# Proto-Shield_v10.net
KiCad netlist of a schematic drawn in EAGLE
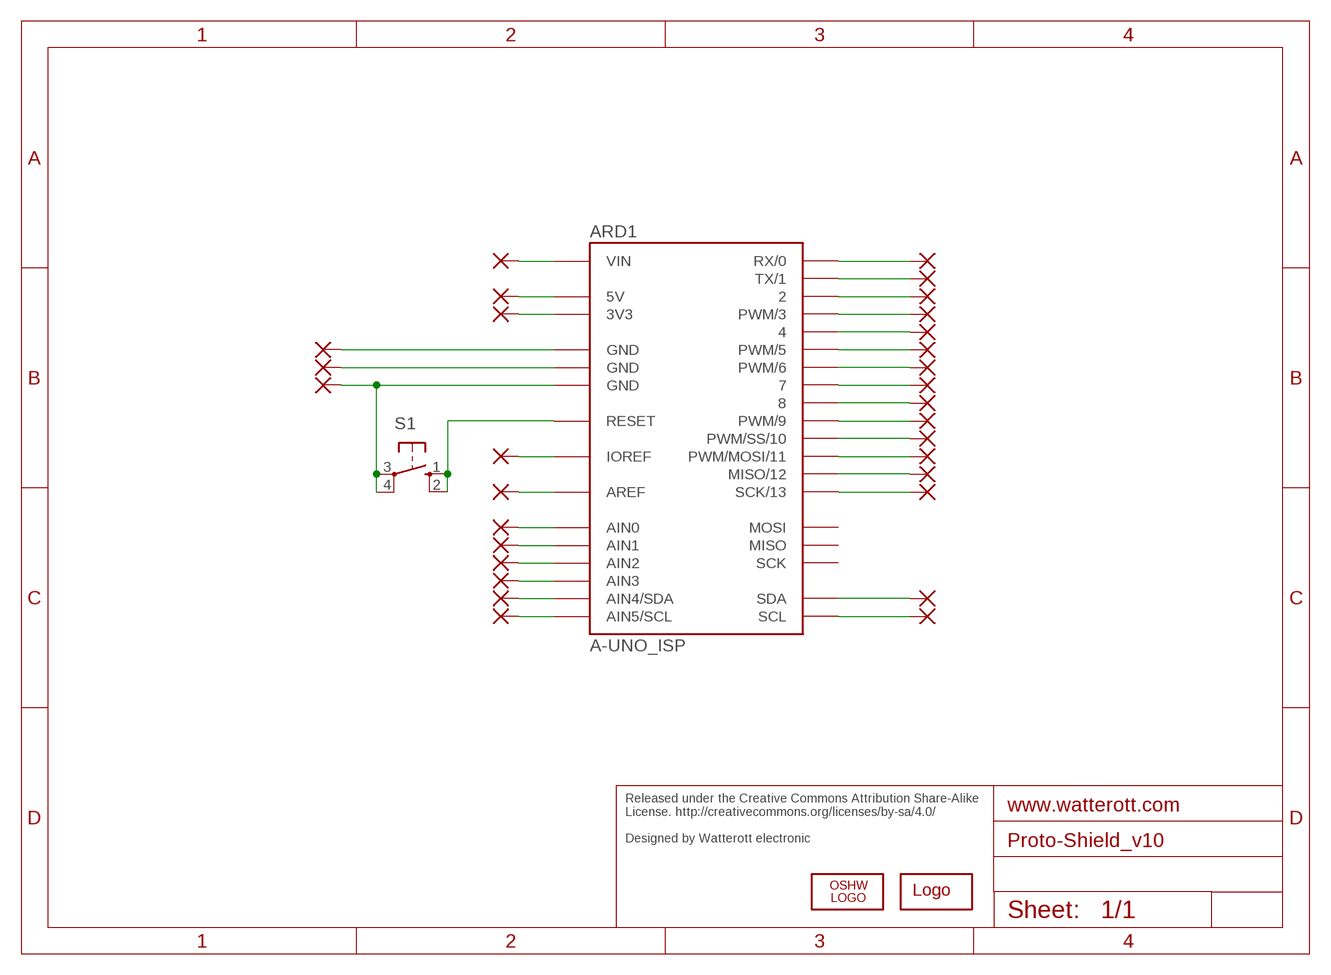
[diagram p0: schematic, sheet 1]

(export (version "E")
  (design (tool "Eeschema 10.0.6"))
  (components
    (comp (ref "ARD1")
      (value "A-UNO_ISP")
      (footprint "eagle-import:A-UNO-ISP")
      (libsource (lib "eagle-import") (part "A-UNO_ISP"))
    )
    (comp (ref "LOGO1")
      (value "OSHW_LOGOX0070")
      (footprint "eagle-import:OSHW_6X70")
      (libsource (lib "eagle-import") (part "OSHW_LOGOX0070"))
    )
    (comp (ref "LOGO2")
      (value "LOGO-S_PLACE_S")
      (footprint "eagle-import:SPARK_TPLACE_S")
      (libsource (lib "eagle-import") (part "LOGO-S_PLACE_S"))
    )
    (comp (ref "PAD1")
      (value "1,6/0,9")
      (footprint "eagle-import:1,6_0,9")
      (libsource (lib "eagle-import") (part "1,6/0,9"))
    )
    (comp (ref "PAD2")
      (value "1,6/0,9")
      (footprint "eagle-import:1,6_0,9")
      (libsource (lib "eagle-import") (part "1,6/0,9"))
    )
    (comp (ref "PAD3")
      (value "1,6/0,9")
      (footprint "eagle-import:1,6_0,9")
      (libsource (lib "eagle-import") (part "1,6/0,9"))
    )
    (comp (ref "PAD4")
      (value "1,6/0,9")
      (footprint "eagle-import:1,6_0,9")
      (libsource (lib "eagle-import") (part "1,6/0,9"))
    )
    (comp (ref "PAD5")
      (value "1,6/0,9")
      (footprint "eagle-import:1,6_0,9")
      (libsource (lib "eagle-import") (part "1,6/0,9"))
    )
    (comp (ref "PAD6")
      (value "1,6/0,9")
      (footprint "eagle-import:1,6_0,9")
      (libsource (lib "eagle-import") (part "1,6/0,9"))
    )
    (comp (ref "PAD7")
      (value "1,6/0,9")
      (footprint "eagle-import:1,6_0,9")
      (libsource (lib "eagle-import") (part "1,6/0,9"))
    )
    (comp (ref "PAD8")
      (value "1,6/0,9")
      (footprint "eagle-import:1,6_0,9")
      (libsource (lib "eagle-import") (part "1,6/0,9"))
    )
    (comp (ref "PAD9")
      (value "1,6/0,9")
      (footprint "eagle-import:1,6_0,9")
      (libsource (lib "eagle-import") (part "1,6/0,9"))
    )
    (comp (ref "PAD10")
      (value "1,6/0,9")
      (footprint "eagle-import:1,6_0,9")
      (libsource (lib "eagle-import") (part "1,6/0,9"))
    )
    (comp (ref "PAD11")
      (value "1,6/0,9")
      (footprint "eagle-import:1,6_0,9")
      (libsource (lib "eagle-import") (part "1,6/0,9"))
    )
    (comp (ref "PAD12")
      (value "1,6/0,9")
      (footprint "eagle-import:1,6_0,9")
      (libsource (lib "eagle-import") (part "1,6/0,9"))
    )
    (comp (ref "PAD13")
      (value "1,6/0,9")
      (footprint "eagle-import:1,6_0,9")
      (libsource (lib "eagle-import") (part "1,6/0,9"))
    )
    (comp (ref "PAD14")
      (value "1,6/0,9")
      (footprint "eagle-import:1,6_0,9")
      (libsource (lib "eagle-import") (part "1,6/0,9"))
    )
    (comp (ref "PAD15")
      (value "1,6/0,9")
      (footprint "eagle-import:1,6_0,9")
      (libsource (lib "eagle-import") (part "1,6/0,9"))
    )
    (comp (ref "PAD16")
      (value "1,6/0,9")
      (footprint "eagle-import:1,6_0,9")
      (libsource (lib "eagle-import") (part "1,6/0,9"))
    )
    (comp (ref "PAD17")
      (value "1,6/0,9")
      (footprint "eagle-import:1,6_0,9")
      (libsource (lib "eagle-import") (part "1,6/0,9"))
    )
    (comp (ref "PAD18")
      (value "1,6/0,9")
      (footprint "eagle-import:1,6_0,9")
      (libsource (lib "eagle-import") (part "1,6/0,9"))
    )
    (comp (ref "PAD19")
      (value "1,6/0,9")
      (footprint "eagle-import:1,6_0,9")
      (libsource (lib "eagle-import") (part "1,6/0,9"))
    )
    (comp (ref "PAD20")
      (value "1,6/0,9")
      (footprint "eagle-import:1,6_0,9")
      (libsource (lib "eagle-import") (part "1,6/0,9"))
    )
    (comp (ref "PAD21")
      (value "1,6/0,9")
      (footprint "eagle-import:1,6_0,9")
      (libsource (lib "eagle-import") (part "1,6/0,9"))
    )
    (comp (ref "PAD22")
      (value "1,6/0,9")
      (footprint "eagle-import:1,6_0,9")
      (libsource (lib "eagle-import") (part "1,6/0,9"))
    )
    (comp (ref "PAD23")
      (value "1,6/0,9")
      (footprint "eagle-import:1,6_0,9")
      (libsource (lib "eagle-import") (part "1,6/0,9"))
    )
    (comp (ref "PAD24")
      (value "1,6/0,9")
      (footprint "eagle-import:1,6_0,9")
      (libsource (lib "eagle-import") (part "1,6/0,9"))
    )
    (comp (ref "PAD25")
      (value "1,6/0,9")
      (footprint "eagle-import:1,6_0,9")
      (libsource (lib "eagle-import") (part "1,6/0,9"))
    )
    (comp (ref "PAD26")
      (value "1,6/0,9")
      (footprint "eagle-import:1,6_0,9")
      (libsource (lib "eagle-import") (part "1,6/0,9"))
    )
    (comp (ref "PAD27")
      (value "1,6/0,9")
      (footprint "eagle-import:1,6_0,9")
      (libsource (lib "eagle-import") (part "1,6/0,9"))
    )
    (comp (ref "PAD28")
      (value "1,6/0,9")
      (footprint "eagle-import:1,6_0,9")
      (libsource (lib "eagle-import") (part "1,6/0,9"))
    )
    (comp (ref "PAD29")
      (value "1,6/0,9")
      (footprint "eagle-import:1,6_0,9")
      (libsource (lib "eagle-import") (part "1,6/0,9"))
    )
    (comp (ref "PAD30")
      (value "1,6/0,9")
      (footprint "eagle-import:1,6_0,9")
      (libsource (lib "eagle-import") (part "1,6/0,9"))
    )
    (comp (ref "S1")
      (value "10-XX")
      (footprint "eagle-import:B3F-10XX")
      (fields (field (name "MPN") "B3F-1000"))
      (libsource (lib "eagle-import") (part "10-XX"))
    )
  )
  (nets
    (net (code "1") (name "Net-(ARD1-AIN0)") (class "Default")
      (node (ref "ARD1") (pin "A0") (pinfunction "AIN0_A0") (pintype "bidirectional"))
      (node (ref "PAD17") (pin "1") (pinfunction "P_1") (pintype "passive"))
    )
    (net (code "2") (name "Net-(ARD1-AIN1)") (class "Default")
      (node (ref "ARD1") (pin "A1") (pinfunction "AIN1_A1") (pintype "bidirectional"))
      (node (ref "PAD18") (pin "1") (pinfunction "P_1") (pintype "passive"))
    )
    (net (code "3") (name "Net-(ARD1-AIN2)") (class "Default")
      (node (ref "ARD1") (pin "A2") (pinfunction "AIN2_A2") (pintype "bidirectional"))
      (node (ref "PAD19") (pin "1") (pinfunction "P_1") (pintype "passive"))
    )
    (net (code "4") (name "Net-(ARD1-AIN3)") (class "Default")
      (node (ref "ARD1") (pin "A3") (pinfunction "AIN3_A3") (pintype "bidirectional"))
      (node (ref "PAD20") (pin "1") (pinfunction "P_1") (pintype "passive"))
    )
    (net (code "5") (name "Net-(ARD1-AIN4{slash}SDA)") (class "Default")
      (node (ref "ARD1") (pin "A4") (pinfunction "AIN4/SDA_A4") (pintype "bidirectional"))
      (node (ref "PAD21") (pin "1") (pinfunction "P_1") (pintype "passive"))
    )
    (net (code "6") (name "Net-(ARD1-AIN5{slash}SCL)") (class "Default")
      (node (ref "ARD1") (pin "A5") (pinfunction "AIN5/SCL_A5") (pintype "bidirectional"))
      (node (ref "PAD22") (pin "1") (pinfunction "P_1") (pintype "passive"))
    )
    (net (code "7") (name "Net-(ARD1-MISO{slash}12)") (class "Default")
      (node (ref "ARD1") (pin "12") (pinfunction "MISO/12_12") (pintype "bidirectional"))
      (node (ref "PAD13") (pin "1") (pinfunction "P_1") (pintype "passive"))
    )
    (net (code "8") (name "Net-(ARD1-PWM{slash}3)") (class "Default")
      (node (ref "ARD1") (pin "3") (pinfunction "PWM/3_3") (pintype "bidirectional"))
      (node (ref "PAD4") (pin "1") (pinfunction "P_1") (pintype "passive"))
    )
    (net (code "9") (name "Net-(ARD1-PWM{slash}5)") (class "Default")
      (node (ref "ARD1") (pin "5") (pinfunction "PWM/5_5") (pintype "bidirectional"))
      (node (ref "PAD6") (pin "1") (pinfunction "P_1") (pintype "passive"))
    )
    (net (code "10") (name "Net-(ARD1-PWM{slash}6)") (class "Default")
      (node (ref "ARD1") (pin "6") (pinfunction "PWM/6_6") (pintype "bidirectional"))
      (node (ref "PAD7") (pin "1") (pinfunction "P_1") (pintype "passive"))
    )
    (net (code "11") (name "Net-(ARD1-PWM{slash}9)") (class "Default")
      (node (ref "ARD1") (pin "9") (pinfunction "PWM/9_9") (pintype "bidirectional"))
      (node (ref "PAD10") (pin "1") (pinfunction "P_1") (pintype "passive"))
    )
    (net (code "12") (name "Net-(ARD1-PWM{slash}MOSI{slash}11)") (class "Default")
      (node (ref "ARD1") (pin "11") (pinfunction "PWM/MOSI/11_11") (pintype "bidirectional"))
      (node (ref "PAD12") (pin "1") (pinfunction "P_1") (pintype "passive"))
    )
    (net (code "13") (name "Net-(ARD1-PWM{slash}SS{slash}10)") (class "Default")
      (node (ref "ARD1") (pin "10") (pinfunction "PWM/SS/10_10") (pintype "bidirectional"))
      (node (ref "PAD11") (pin "1") (pinfunction "P_1") (pintype "passive"))
    )
    (net (code "14") (name "Net-(ARD1-RESET)") (class "Default")
      (node (ref "ARD1") (pin "RST") (pinfunction "RESET_RST") (pintype "bidirectional"))
      (node (ref "S1") (pin "1") (pinfunction "S_1") (pintype "passive"))
      (node (ref "S1") (pin "2") (pinfunction "S1_2") (pintype "passive"))
    )
    (net (code "15") (name "Net-(ARD1-RX{slash}0)") (class "Default")
      (node (ref "ARD1") (pin "0") (pinfunction "RX/0_0") (pintype "bidirectional"))
      (node (ref "PAD1") (pin "1") (pinfunction "P_1") (pintype "passive"))
    )
    (net (code "16") (name "Net-(ARD1-SCK{slash}13)") (class "Default")
      (node (ref "ARD1") (pin "13") (pinfunction "SCK/13_13") (pintype "bidirectional"))
      (node (ref "PAD14") (pin "1") (pinfunction "P_1") (pintype "passive"))
    )
    (net (code "17") (name "Net-(ARD1-TX{slash}1)") (class "Default")
      (node (ref "ARD1") (pin "1") (pinfunction "TX/1_1") (pintype "bidirectional"))
      (node (ref "PAD2") (pin "1") (pinfunction "P_1") (pintype "passive"))
    )
    (net (code "18") (name "Net-(PAD3-P)") (class "Default")
      (node (ref "ARD1") (pin "2") (pinfunction "2_2") (pintype "bidirectional"))
      (node (ref "PAD3") (pin "1") (pinfunction "P_1") (pintype "passive"))
    )
    (net (code "19") (name "Net-(PAD5-P)") (class "Default")
      (node (ref "ARD1") (pin "4") (pinfunction "4_4") (pintype "bidirectional"))
      (node (ref "PAD5") (pin "1") (pinfunction "P_1") (pintype "passive"))
    )
    (net (code "20") (name "Net-(PAD8-P)") (class "Default")
      (node (ref "ARD1") (pin "7") (pinfunction "7_7") (pintype "bidirectional"))
      (node (ref "PAD8") (pin "1") (pinfunction "P_1") (pintype "passive"))
    )
    (net (code "21") (name "Net-(PAD9-P)") (class "Default")
      (node (ref "ARD1") (pin "8") (pinfunction "8_8") (pintype "bidirectional"))
      (node (ref "PAD9") (pin "1") (pinfunction "P_1") (pintype "passive"))
    )
    (net (code "22") (name "Net-(PAD15-P)") (class "Default")
      (node (ref "ARD1") (pin "SDA") (pinfunction "SDA_SDA") (pintype "bidirectional"))
      (node (ref "PAD15") (pin "1") (pinfunction "P_1") (pintype "passive"))
    )
    (net (code "23") (name "Net-(PAD16-P)") (class "Default")
      (node (ref "ARD1") (pin "SCL") (pinfunction "SCL_SCL") (pintype "bidirectional"))
      (node (ref "PAD16") (pin "1") (pinfunction "P_1") (pintype "passive"))
    )
    (net (code "24") (name "Net-(PAD23-P)") (class "Default")
      (node (ref "ARD1") (pin "AREF") (pinfunction "AREF_AREF") (pintype "power_in"))
      (node (ref "PAD23") (pin "1") (pinfunction "P_1") (pintype "passive"))
    )
    (net (code "25") (name "Net-(PAD24-P)") (class "Default")
      (node (ref "ARD1") (pin "IOREF") (pinfunction "IOREF_IOREF") (pintype "power_in"))
      (node (ref "PAD24") (pin "1") (pinfunction "P_1") (pintype "passive"))
    )
    (net (code "26") (name "Net-(PAD25-P)") (class "Default")
      (node (ref "ARD1") (pin "GND@3") (pinfunction "GND_GND@3") (pintype "power_in"))
      (node (ref "PAD25") (pin "1") (pinfunction "P_1") (pintype "passive"))
      (node (ref "S1") (pin "3") (pinfunction "P_3") (pintype "passive"))
      (node (ref "S1") (pin "4") (pinfunction "P1_4") (pintype "passive"))
    )
    (net (code "27") (name "Net-(PAD26-P)") (class "Default")
      (node (ref "ARD1") (pin "GND@2") (pinfunction "GND_GND@2") (pintype "power_in"))
      (node (ref "PAD26") (pin "1") (pinfunction "P_1") (pintype "passive"))
    )
    (net (code "28") (name "Net-(PAD27-P)") (class "Default")
      (node (ref "ARD1") (pin "GND@1") (pinfunction "GND_GND@1") (pintype "power_in"))
      (node (ref "PAD27") (pin "1") (pinfunction "P_1") (pintype "passive"))
    )
    (net (code "29") (name "Net-(PAD28-P)") (class "Default")
      (node (ref "ARD1") (pin "3V3") (pinfunction "3V3_3V3") (pintype "power_in"))
      (node (ref "PAD28") (pin "1") (pinfunction "P_1") (pintype "passive"))
    )
    (net (code "30") (name "Net-(PAD29-P)") (class "Default")
      (node (ref "ARD1") (pin "5V") (pinfunction "5V_5V") (pintype "power_in"))
      (node (ref "PAD29") (pin "1") (pinfunction "P_1") (pintype "passive"))
    )
    (net (code "31") (name "Net-(PAD30-P)") (class "Default")
      (node (ref "ARD1") (pin "VIN") (pinfunction "VIN_VIN") (pintype "power_in"))
      (node (ref "PAD30") (pin "1") (pinfunction "P_1") (pintype "passive"))
    )
    (net (code "32") (name "unconnected-(ARD1-PadMISO)") (class "Default")
      (node (ref "ARD1") (pin "MISO") (pinfunction "MISO_MISO") (pintype "bidirectional"))
    )
    (net (code "33") (name "unconnected-(ARD1-PadMOSI)") (class "Default")
      (node (ref "ARD1") (pin "MOSI") (pinfunction "MOSI_MOSI") (pintype "bidirectional"))
    )
    (net (code "34") (name "unconnected-(ARD1-PadSCK)") (class "Default")
      (node (ref "ARD1") (pin "SCK") (pinfunction "SCK_SCK") (pintype "bidirectional"))
    )
  )
)
